# Main.net
KiCad netlist of a schematic drawn in Altium Designer
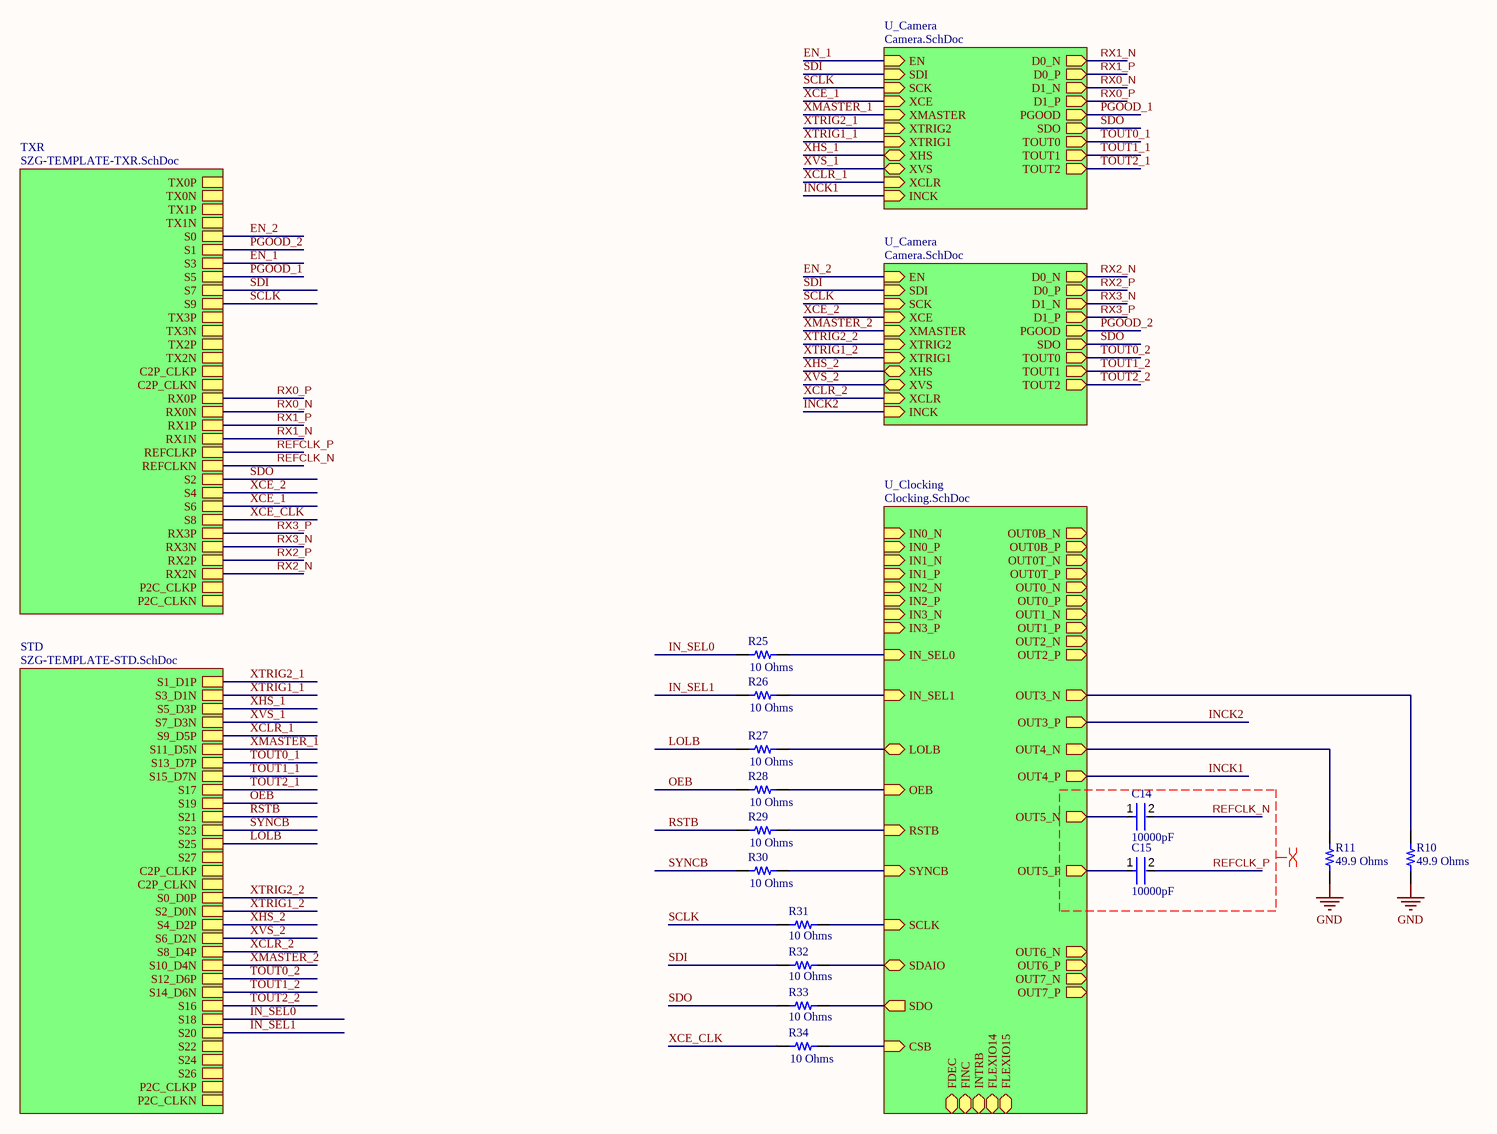
[diagram p0: Main.SchDoc]

(export (version "E")
  (design (tool "Eeschema 10.0.6"))
  (components
    (comp (ref "C14")
      (value "10000pF")
      (footprint "FP-GRM033-0_03-MFG")
      (description "CAP CER 10000PF 25V X5R 0201")
      (libsource (lib "SimulaVR") (part "b4654b650e69147ec39a6b967a45e02"))
    )
    (comp (ref "C15")
      (value "10000pF")
      (footprint "FP-GRM033-0_03-MFG")
      (description "CAP CER 10000PF 25V X5R 0201")
      (libsource (lib "SimulaVR") (part "b4654b650e69147ec39a6b967a45e02"))
    )
    (comp (ref "R10")
      (value "49.9 Ohms")
      (footprint "RES 0402_1005")
      (description "RES SMD 49.9 OHM 1% 1/10W 0402")
      (fields
        (field (name "PART NUMBER") "ERJ-2RKF49R9X")
        (field (name "MANUFACTURER") "Panasonic Electronic Components")
      )
      (libsource (lib "Celestial Altium Library - altium_library") (part "Resistor"))
    )
    (comp (ref "R11")
      (value "49.9 Ohms")
      (footprint "RES 0402_1005")
      (description "RES SMD 49.9 OHM 1% 1/10W 0402")
      (fields
        (field (name "PART NUMBER") "ERJ-2RKF49R9X")
        (field (name "MANUFACTURER") "Panasonic Electronic Components")
      )
      (libsource (lib "Celestial Altium Library - altium_library") (part "Resistor"))
    )
    (comp (ref "R25")
      (value "10 Ohms")
      (footprint "RES 0201_0603")
      (description "RES SMD 10 OHM 1% 1/20W 0201")
      (fields
        (field (name "PART NUMBER") "CRG0201F10R")
        (field (name "MANUFACTURER") "TE Connectivity Passive Product")
      )
      (libsource (lib "Celestial Altium Library - altium_library") (part "Resistor"))
    )
    (comp (ref "R26")
      (value "10 Ohms")
      (footprint "RES 0201_0603")
      (description "RES SMD 10 OHM 1% 1/20W 0201")
      (fields
        (field (name "PART NUMBER") "CRG0201F10R")
        (field (name "MANUFACTURER") "TE Connectivity Passive Product")
      )
      (libsource (lib "Celestial Altium Library - altium_library") (part "Resistor"))
    )
    (comp (ref "R27")
      (value "10 Ohms")
      (footprint "RES 0201_0603")
      (description "RES SMD 10 OHM 1% 1/20W 0201")
      (fields
        (field (name "PART NUMBER") "CRG0201F10R")
        (field (name "MANUFACTURER") "TE Connectivity Passive Product")
      )
      (libsource (lib "Celestial Altium Library - altium_library") (part "Resistor"))
    )
    (comp (ref "R28")
      (value "10 Ohms")
      (footprint "RES 0201_0603")
      (description "RES SMD 10 OHM 1% 1/20W 0201")
      (fields
        (field (name "PART NUMBER") "CRG0201F10R")
        (field (name "MANUFACTURER") "TE Connectivity Passive Product")
      )
      (libsource (lib "Celestial Altium Library - altium_library") (part "Resistor"))
    )
    (comp (ref "R29")
      (value "10 Ohms")
      (footprint "RES 0201_0603")
      (description "RES SMD 10 OHM 1% 1/20W 0201")
      (fields
        (field (name "PART NUMBER") "CRG0201F10R")
        (field (name "MANUFACTURER") "TE Connectivity Passive Product")
      )
      (libsource (lib "Celestial Altium Library - altium_library") (part "Resistor"))
    )
    (comp (ref "R30")
      (value "10 Ohms")
      (footprint "RES 0201_0603")
      (description "RES SMD 10 OHM 1% 1/20W 0201")
      (fields
        (field (name "PART NUMBER") "CRG0201F10R")
        (field (name "MANUFACTURER") "TE Connectivity Passive Product")
      )
      (libsource (lib "Celestial Altium Library - altium_library") (part "Resistor"))
    )
    (comp (ref "R31")
      (value "10 Ohms")
      (footprint "RES 0201_0603")
      (description "RES SMD 10 OHM 1% 1/20W 0201")
      (fields
        (field (name "PART NUMBER") "CRG0201F10R")
        (field (name "MANUFACTURER") "TE Connectivity Passive Product")
      )
      (libsource (lib "Celestial Altium Library - altium_library") (part "Resistor"))
    )
    (comp (ref "R32")
      (value "10 Ohms")
      (footprint "RES 0201_0603")
      (description "RES SMD 10 OHM 1% 1/20W 0201")
      (fields
        (field (name "PART NUMBER") "CRG0201F10R")
        (field (name "MANUFACTURER") "TE Connectivity Passive Product")
      )
      (libsource (lib "Celestial Altium Library - altium_library") (part "Resistor"))
    )
    (comp (ref "R33")
      (value "10 Ohms")
      (footprint "RES 0201_0603")
      (description "RES SMD 10 OHM 1% 1/20W 0201")
      (fields
        (field (name "PART NUMBER") "CRG0201F10R")
        (field (name "MANUFACTURER") "TE Connectivity Passive Product")
      )
      (libsource (lib "Celestial Altium Library - altium_library") (part "Resistor"))
    )
    (comp (ref "R34")
      (value "10 Ohms")
      (footprint "RES 0201_0603")
      (description "RES SMD 10 OHM 1% 1/20W 0201")
      (fields
        (field (name "PART NUMBER") "CRG0201F10R")
        (field (name "MANUFACTURER") "TE Connectivity Passive Product")
      )
      (libsource (lib "Celestial Altium Library - altium_library") (part "Resistor"))
    )
  )
  (nets
    (net (code "5") (name "/CSB") (class "Default")
      (node (ref "R34") (pin "2") (pinfunction "2_2") (pintype "passive"))
    )
    (net (code "23") (name "/IN_SEL0") (class "Default")
      (node (ref "R25") (pin "1") (pinfunction "1_1") (pintype "passive"))
    )
    (net (code "24") (name "/IN_SEL0_1") (class "Default")
      (node (ref "R25") (pin "2") (pinfunction "2_2") (pintype "passive"))
    )
    (net (code "25") (name "/IN_SEL1") (class "Default")
      (node (ref "R26") (pin "1") (pinfunction "1_1") (pintype "passive"))
    )
    (net (code "26") (name "/IN_SEL1_1") (class "Default")
      (node (ref "R26") (pin "2") (pinfunction "2_2") (pintype "passive"))
    )
    (net (code "27") (name "/LOLB") (class "Default")
      (node (ref "R27") (pin "1") (pinfunction "1_1") (pintype "passive"))
    )
    (net (code "28") (name "/LOLB_1") (class "Default")
      (node (ref "R27") (pin "2") (pinfunction "2_2") (pintype "passive"))
    )
    (net (code "29") (name "/OEB") (class "Default")
      (node (ref "R28") (pin "1") (pinfunction "1_1") (pintype "passive"))
    )
    (net (code "30") (name "/OEB_1") (class "Default")
      (node (ref "R28") (pin "2") (pinfunction "2_2") (pintype "passive"))
    )
    (net (code "41") (name "/OUT3_N") (class "Default")
      (node (ref "R10") (pin "2") (pinfunction "2_2") (pintype "passive"))
    )
    (net (code "42") (name "/OUT4_N") (class "Default")
      (node (ref "R11") (pin "2") (pinfunction "2_2") (pintype "passive"))
    )
    (net (code "43") (name "/OUT5_N") (class "Default")
      (node (ref "C14") (pin "1") (pinfunction "1_1") (pintype "passive"))
    )
    (net (code "44") (name "/OUT5_P") (class "Default")
      (node (ref "C15") (pin "1") (pinfunction "1_1") (pintype "passive"))
    )
    (net (code "55") (name "/REFCLK_N") (class "Default")
      (node (ref "C14") (pin "2") (pinfunction "2_2") (pintype "passive"))
    )
    (net (code "56") (name "/REFCLK_P") (class "Default")
      (node (ref "C15") (pin "2") (pinfunction "2_2") (pintype "passive"))
    )
    (net (code "57") (name "/RSTB") (class "Default")
      (node (ref "R29") (pin "1") (pinfunction "1_1") (pintype "passive"))
    )
    (net (code "58") (name "/RSTB_1") (class "Default")
      (node (ref "R29") (pin "2") (pinfunction "2_2") (pintype "passive"))
    )
    (net (code "71") (name "/SCLK") (class "Default")
      (node (ref "R31") (pin "1") (pinfunction "1_1") (pintype "passive"))
    )
    (net (code "72") (name "/SCLK_1") (class "Default")
      (node (ref "R31") (pin "2") (pinfunction "2_2") (pintype "passive"))
    )
    (net (code "73") (name "/SDAIO") (class "Default")
      (node (ref "R32") (pin "2") (pinfunction "2_2") (pintype "passive"))
    )
    (net (code "74") (name "/SDI") (class "Default")
      (node (ref "R32") (pin "1") (pinfunction "1_1") (pintype "passive"))
    )
    (net (code "75") (name "/SDO") (class "Default")
      (node (ref "R33") (pin "1") (pinfunction "1_1") (pintype "passive"))
    )
    (net (code "76") (name "/SDO_1") (class "Default")
      (node (ref "R33") (pin "2") (pinfunction "2_2") (pintype "passive"))
    )
    (net (code "77") (name "/SYNCB") (class "Default")
      (node (ref "R30") (pin "1") (pinfunction "1_1") (pintype "passive"))
    )
    (net (code "78") (name "/SYNCB_1") (class "Default")
      (node (ref "R30") (pin "2") (pinfunction "2_2") (pintype "passive"))
    )
    (net (code "95") (name "/XCE_CLK") (class "Default")
      (node (ref "R34") (pin "1") (pinfunction "1_1") (pintype "passive"))
    )
    (net (code "108") (name "GND") (class "Default")
      (node (ref "R10") (pin "1") (pinfunction "1_1") (pintype "passive"))
      (node (ref "R11") (pin "1") (pinfunction "1_1") (pintype "passive"))
    )
  )
)
